# BLE-2541simple.net
KiCad netlist of a schematic drawn in Altium Designer
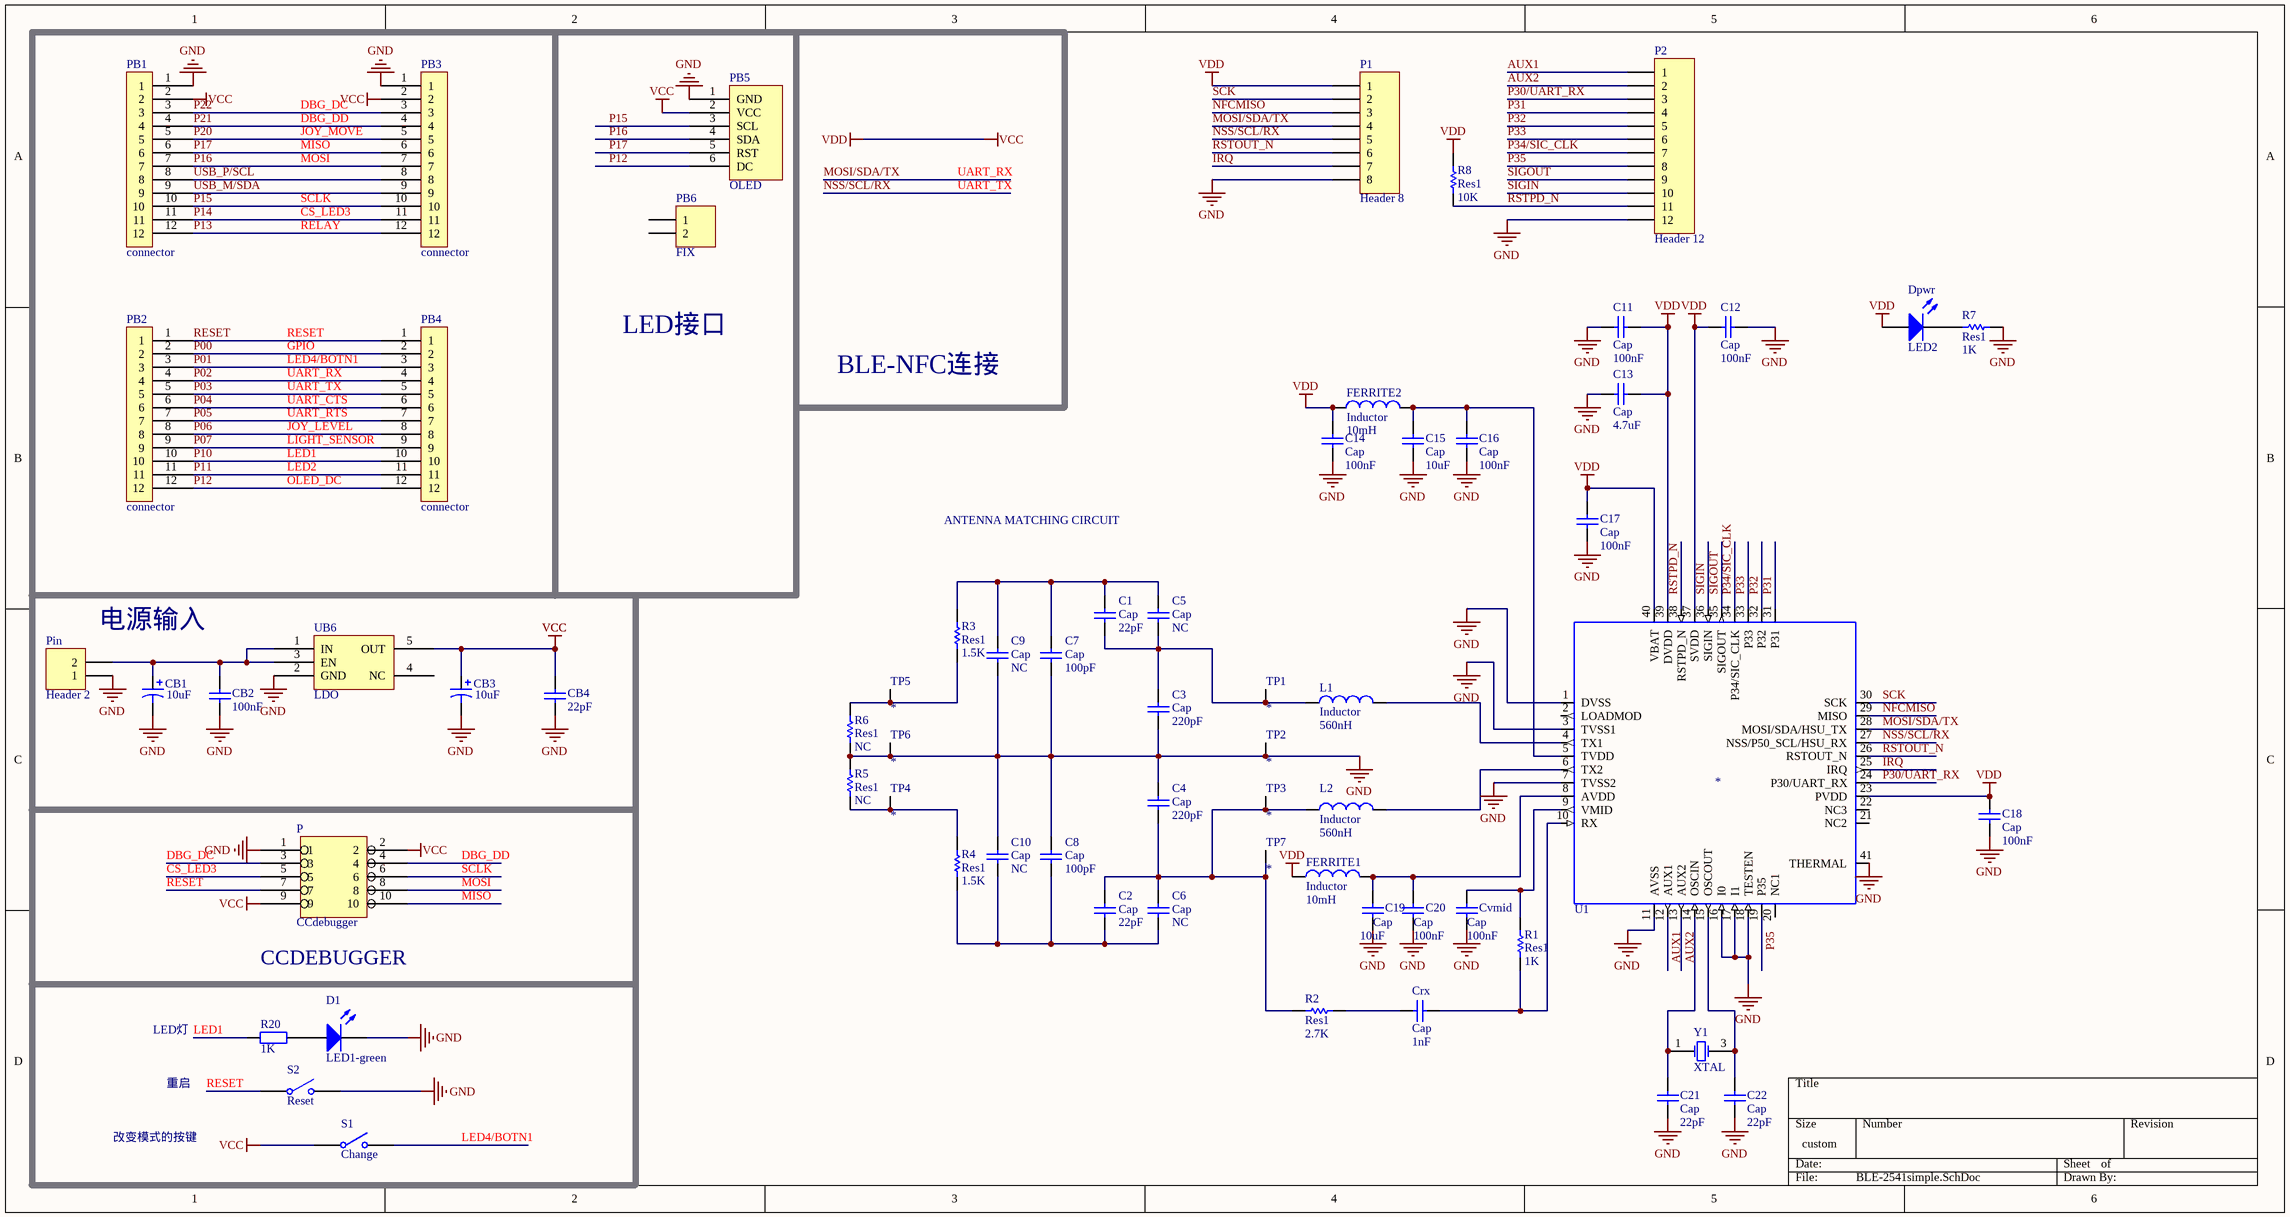
[diagram p0: BLE-2541simple.SchDoc]

(export (version "E")
  (design (tool "Eeschema 10.0.6"))
  (components
    (comp (ref "C1")
      (value "Cap")
      (footprint "6-0805_M")
      (description "Capacitor")
      (fields (field (name "ALTIUM_VALUE") "22pF") (field (name "PUBLISHER") "Altium Limited"))
      (libsource (lib "Miscellaneous Devices") (part "Cap"))
    )
    (comp (ref "C2")
      (value "Cap")
      (footprint "6-0805_M")
      (description "Capacitor")
      (fields (field (name "ALTIUM_VALUE") "22pF") (field (name "PUBLISHER") "Altium Limited"))
      (libsource (lib "Miscellaneous Devices") (part "Cap"))
    )
    (comp (ref "C3")
      (value "Cap")
      (footprint "6-0805_M")
      (description "Capacitor")
      (fields (field (name "ALTIUM_VALUE") "220pF") (field (name "PUBLISHER") "Altium Limited"))
      (libsource (lib "Miscellaneous Devices") (part "Cap"))
    )
    (comp (ref "C4")
      (value "Cap")
      (footprint "6-0805_M")
      (description "Capacitor")
      (fields (field (name "ALTIUM_VALUE") "220pF") (field (name "PUBLISHER") "Altium Limited"))
      (libsource (lib "Miscellaneous Devices") (part "Cap"))
    )
    (comp (ref "C5")
      (value "Cap")
      (footprint "6-0805_M")
      (description "Capacitor")
      (fields (field (name "ALTIUM_VALUE") "NC") (field (name "PUBLISHER") "Altium Limited"))
      (libsource (lib "Miscellaneous Devices") (part "Cap"))
    )
    (comp (ref "C6")
      (value "Cap")
      (footprint "6-0805_M")
      (description "Capacitor")
      (fields (field (name "ALTIUM_VALUE") "NC") (field (name "PUBLISHER") "Altium Limited"))
      (libsource (lib "Miscellaneous Devices") (part "Cap"))
    )
    (comp (ref "C7")
      (value "Cap")
      (footprint "6-0805_M")
      (description "Capacitor")
      (fields (field (name "ALTIUM_VALUE") "100pF") (field (name "PUBLISHER") "Altium Limited"))
      (libsource (lib "Miscellaneous Devices") (part "Cap"))
    )
    (comp (ref "C8")
      (value "Cap")
      (footprint "6-0805_M")
      (description "Capacitor")
      (fields (field (name "ALTIUM_VALUE") "100pF") (field (name "PUBLISHER") "Altium Limited"))
      (libsource (lib "Miscellaneous Devices") (part "Cap"))
    )
    (comp (ref "C9")
      (value "Cap")
      (footprint "6-0805_M")
      (description "Capacitor")
      (fields (field (name "ALTIUM_VALUE") "NC") (field (name "PUBLISHER") "Altium Limited"))
      (libsource (lib "Miscellaneous Devices") (part "Cap"))
    )
    (comp (ref "C10")
      (value "Cap")
      (footprint "6-0805_M")
      (description "Capacitor")
      (fields (field (name "ALTIUM_VALUE") "NC") (field (name "PUBLISHER") "Altium Limited"))
      (libsource (lib "Miscellaneous Devices") (part "Cap"))
    )
    (comp (ref "C11")
      (value "Cap")
      (footprint "6-0805_M")
      (description "Capacitor")
      (fields (field (name "ALTIUM_VALUE") "100nF") (field (name "PUBLISHER") "Altium Limited"))
      (libsource (lib "Miscellaneous Devices") (part "Cap"))
    )
    (comp (ref "C12")
      (value "Cap")
      (footprint "6-0805_M")
      (description "Capacitor")
      (fields (field (name "ALTIUM_VALUE") "100nF") (field (name "PUBLISHER") "Altium Limited"))
      (libsource (lib "Miscellaneous Devices") (part "Cap"))
    )
    (comp (ref "C13")
      (value "Cap")
      (footprint "6-0805_M")
      (description "Capacitor")
      (fields (field (name "ALTIUM_VALUE") "4.7uF") (field (name "PUBLISHER") "Altium Limited"))
      (libsource (lib "Miscellaneous Devices") (part "Cap"))
    )
    (comp (ref "C14")
      (value "Cap")
      (footprint "6-0805_M")
      (description "Capacitor")
      (fields (field (name "ALTIUM_VALUE") "100nF") (field (name "PUBLISHER") "Altium Limited"))
      (libsource (lib "Miscellaneous Devices") (part "Cap"))
    )
    (comp (ref "C15")
      (value "Cap")
      (footprint "6-0805_M")
      (description "Capacitor")
      (fields (field (name "ALTIUM_VALUE") "10uF") (field (name "PUBLISHER") "Altium Limited"))
      (libsource (lib "Miscellaneous Devices") (part "Cap"))
    )
    (comp (ref "C16")
      (value "Cap")
      (footprint "6-0805_M")
      (description "Capacitor")
      (fields (field (name "ALTIUM_VALUE") "100nF") (field (name "PUBLISHER") "Altium Limited"))
      (libsource (lib "Miscellaneous Devices") (part "Cap"))
    )
    (comp (ref "C17")
      (value "Cap")
      (footprint "6-0805_M")
      (description "Capacitor")
      (fields (field (name "ALTIUM_VALUE") "100nF") (field (name "PUBLISHER") "Altium Limited"))
      (libsource (lib "Miscellaneous Devices") (part "Cap"))
    )
    (comp (ref "C18")
      (value "Cap")
      (footprint "6-0805_M")
      (description "Capacitor")
      (fields (field (name "ALTIUM_VALUE") "100nF") (field (name "PUBLISHER") "Altium Limited"))
      (libsource (lib "Miscellaneous Devices") (part "Cap"))
    )
    (comp (ref "C19")
      (value "Cap")
      (footprint "6-0805_M")
      (description "Capacitor")
      (fields (field (name "ALTIUM_VALUE") "10uF") (field (name "PUBLISHER") "Altium Limited"))
      (libsource (lib "Miscellaneous Devices") (part "Cap"))
    )
    (comp (ref "C20")
      (value "Cap")
      (footprint "6-0805_M")
      (description "Capacitor")
      (fields (field (name "ALTIUM_VALUE") "100nF") (field (name "PUBLISHER") "Altium Limited"))
      (libsource (lib "Miscellaneous Devices") (part "Cap"))
    )
    (comp (ref "C21")
      (value "Cap")
      (footprint "6-0805_M")
      (description "Capacitor")
      (fields (field (name "ALTIUM_VALUE") "22pF") (field (name "PUBLISHER") "Altium Limited"))
      (libsource (lib "Miscellaneous Devices") (part "Cap"))
    )
    (comp (ref "C22")
      (value "Cap")
      (footprint "6-0805_M")
      (description "Capacitor")
      (fields (field (name "ALTIUM_VALUE") "22pF") (field (name "PUBLISHER") "Altium Limited"))
      (libsource (lib "Miscellaneous Devices") (part "Cap"))
    )
    (comp (ref "CB1")
      (value "10uF")
      (footprint "0805-SMALL")
      (description "Polarized Capacitor (Radial)")
      (fields (field (name "Comment") "Cap Pol1") (field (name "PUBLISHER") "Altium Limited"))
      (libsource (lib "Miscellaneous Devices") (part "Cap Pol1"))
    )
    (comp (ref "CB2")
      (value "100nF")
      (footprint "0805-SMALL")
      (description "Capacitor")
      (fields (field (name "Comment") "Cap") (field (name "PUBLISHER") "Altium Limited"))
      (libsource (lib "Miscellaneous Devices") (part "Cap"))
    )
    (comp (ref "CB3")
      (value "10uF")
      (footprint "0805-SMALL")
      (description "Polarized Capacitor (Radial)")
      (fields (field (name "Comment") "Cap Pol1") (field (name "PUBLISHER") "Altium Limited"))
      (libsource (lib "Miscellaneous Devices") (part "Cap Pol1"))
    )
    (comp (ref "CB4")
      (value "22pF")
      (footprint "0805-SMALL")
      (description "Capacitor")
      (fields (field (name "Comment") "Cap") (field (name "PUBLISHER") "Altium Limited"))
      (libsource (lib "Miscellaneous Devices") (part "Cap"))
    )
    (comp (ref "Crx")
      (value "Cap")
      (footprint "6-0805_M")
      (description "Capacitor")
      (fields (field (name "ALTIUM_VALUE") "1nF") (field (name "PUBLISHER") "Altium Limited"))
      (libsource (lib "Miscellaneous Devices") (part "Cap"))
    )
    (comp (ref "Cvmid")
      (value "Cap")
      (footprint "6-0805_M")
      (description "Capacitor")
      (fields (field (name "ALTIUM_VALUE") "100nF") (field (name "PUBLISHER") "Altium Limited"))
      (libsource (lib "Miscellaneous Devices") (part "Cap"))
    )
    (comp (ref "D1")
      (value "LED1-green")
      (footprint "3.2X1.6X1.1")
      (description "Typical RED, GREEN, YELLOW, AMBER GaAs LED")
      (fields (field (name "PUBLISHER") "Altium Limited"))
      (libsource (lib "Miscellaneous Devices") (part "LED2"))
    )
    (comp (ref "Dpwr")
      (value "LED2")
      (footprint "6-0805_M")
      (description "Typical RED, GREEN, YELLOW, AMBER GaAs LED")
      (fields (field (name "PUBLISHER") "Altium Limited"))
      (libsource (lib "Miscellaneous Devices") (part "LED2"))
    )
    (comp (ref "FERRITE1")
      (value "Inductor")
      (footprint "6-0805_M")
      (fields (field (name "ALTIUM_VALUE") "10mH") (field (name "PUBLISHER") "Altium Limited"))
      (libsource (lib "Miscellaneous Devices") (part "Inductor"))
    )
    (comp (ref "FERRITE2")
      (value "Inductor")
      (footprint "6-0805_M")
      (fields (field (name "ALTIUM_VALUE") "10mH") (field (name "PUBLISHER") "Altium Limited"))
      (libsource (lib "Miscellaneous Devices") (part "Inductor"))
    )
    (comp (ref "L1")
      (value "Inductor")
      (footprint "6-0805_M")
      (fields (field (name "ALTIUM_VALUE") "560nH") (field (name "PUBLISHER") "Altium Limited"))
      (libsource (lib "Miscellaneous Devices") (part "Inductor"))
    )
    (comp (ref "L2")
      (value "Inductor")
      (footprint "6-0805_M")
      (fields (field (name "ALTIUM_VALUE") "560nH") (field (name "PUBLISHER") "Altium Limited"))
      (libsource (lib "Miscellaneous Devices") (part "Inductor"))
    )
    (comp (ref "P")
      (value "CCdebugger")
      (footprint "M-IDC10")
      (libsource (lib "Schlib1") (part "CCdebugger"))
    )
    (comp (ref "P1")
      (value "Header 8")
      (footprint "HDR1X8")
      (description "Header, 8-Pin")
      (fields (field (name "PUBLISHER") "Altium Limited"))
      (libsource (lib "Miscellaneous Connectors") (part "Header 8"))
    )
    (comp (ref "P2")
      (value "Header 12")
      (footprint "HDR1X12")
      (description "Header, 12-Pin")
      (fields (field (name "PUBLISHER") "Altium Limited"))
      (libsource (lib "Miscellaneous Connectors") (part "Header 12"))
    )
    (comp (ref "PB1") (value "connector") (footprint "M-IDC12M") (libsource (lib "") (part "connector_1")))
    (comp (ref "PB2") (value "connector") (footprint "M-IDC12M") (libsource (lib "") (part "connector_1")))
    (comp (ref "PB3")
      (value "connector")
      (footprint "M-IDC12")
      (libsource (lib "Schlib1") (part "connector"))
    )
    (comp (ref "PB4")
      (value "connector")
      (footprint "M-IDC12")
      (libsource (lib "Schlib1") (part "connector"))
    )
    (comp (ref "PB5") (value "OLED") (footprint "M-SIP6") (libsource (lib "Schlib1") (part "OLED")))
    (comp (ref "PB6")
      (value "FIX")
      (footprint "M-SIP2")
      (description "Header, 2-Pin")
      (fields (field (name "PUBLISHER") "Altium Limited"))
      (libsource (lib "") (part "Header 2_1"))
    )
    (comp (ref "Pin")
      (value "Header 2")
      (footprint "M-SIP2")
      (description "Header, 2-Pin")
      (fields (field (name "PUBLISHER") "Altium Limited"))
      (libsource (lib "Miscellaneous Connectors") (part "Header 2"))
    )
    (comp (ref "R1")
      (value "Res1")
      (footprint "6-0805_M")
      (description "Resistor")
      (fields (field (name "ALTIUM_VALUE") "1K") (field (name "PUBLISHER") "Altium Limited"))
      (libsource (lib "Miscellaneous Devices") (part "Res1"))
    )
    (comp (ref "R2")
      (value "Res1")
      (footprint "6-0805_M")
      (description "Resistor")
      (fields (field (name "ALTIUM_VALUE") "2.7K") (field (name "PUBLISHER") "Altium Limited"))
      (libsource (lib "Miscellaneous Devices") (part "Res1"))
    )
    (comp (ref "R3")
      (value "Res1")
      (footprint "6-0805_M")
      (description "Resistor")
      (fields (field (name "ALTIUM_VALUE") "1.5K") (field (name "PUBLISHER") "Altium Limited"))
      (libsource (lib "Miscellaneous Devices") (part "Res1"))
    )
    (comp (ref "R4")
      (value "Res1")
      (footprint "6-0805_M")
      (description "Resistor")
      (fields (field (name "ALTIUM_VALUE") "1.5K") (field (name "PUBLISHER") "Altium Limited"))
      (libsource (lib "Miscellaneous Devices") (part "Res1"))
    )
    (comp (ref "R5")
      (value "Res1")
      (footprint "6-0805_M")
      (description "Resistor")
      (fields (field (name "ALTIUM_VALUE") "NC") (field (name "PUBLISHER") "Altium Limited"))
      (libsource (lib "Miscellaneous Devices") (part "Res1"))
    )
    (comp (ref "R6")
      (value "Res1")
      (footprint "6-0805_M")
      (description "Resistor")
      (fields (field (name "ALTIUM_VALUE") "NC") (field (name "PUBLISHER") "Altium Limited"))
      (libsource (lib "Miscellaneous Devices") (part "Res1"))
    )
    (comp (ref "R7")
      (value "Res1")
      (footprint "6-0805_M")
      (description "Resistor")
      (fields (field (name "ALTIUM_VALUE") "1K") (field (name "PUBLISHER") "Altium Limited"))
      (libsource (lib "Miscellaneous Devices") (part "Res1"))
    )
    (comp (ref "R8")
      (value "Res1")
      (footprint "6-0805_M")
      (description "Resistor")
      (fields (field (name "ALTIUM_VALUE") "10K") (field (name "PUBLISHER") "Altium Limited"))
      (libsource (lib "Miscellaneous Devices") (part "Res1"))
    )
    (comp (ref "R20")
      (value "1K")
      (footprint "0805-SMALL")
      (description "Resistor")
      (fields (field (name "Comment") "Res2") (field (name "PUBLISHER") "Altium Limited"))
      (libsource (lib "Miscellaneous Devices") (part "Res2"))
    )
    (comp (ref "S1")
      (value "Change")
      (footprint "MY-KEY1")
      (description "Single-Pole, Single-Throw Switch")
      (fields (field (name "PUBLISHER") "Altium Limited"))
      (libsource (lib "Miscellaneous Devices") (part "SW-SPST"))
    )
    (comp (ref "S2")
      (value "Reset")
      (footprint "MY-KEY1")
      (description "Single-Pole, Single-Throw Switch")
      (fields (field (name "PUBLISHER") "Altium Limited"))
      (libsource (lib "Miscellaneous Devices") (part "SW-SPST"))
    )
    (comp (ref "TP1")
      (value "*")
      (footprint "PCBComponent_1")
      (libsource (lib "microbuilder") (part "TESTPOINTPAD"))
    )
    (comp (ref "TP2")
      (value "*")
      (footprint "PCBComponent_1")
      (libsource (lib "microbuilder") (part "TESTPOINTPAD"))
    )
    (comp (ref "TP3")
      (value "*")
      (footprint "PCBComponent_1")
      (libsource (lib "microbuilder") (part "TESTPOINTPAD"))
    )
    (comp (ref "TP4")
      (value "*")
      (footprint "PCBComponent_1")
      (libsource (lib "microbuilder") (part "TESTPOINTPAD"))
    )
    (comp (ref "TP5")
      (value "*")
      (footprint "PCBComponent_1")
      (libsource (lib "microbuilder") (part "TESTPOINTPAD"))
    )
    (comp (ref "TP6")
      (value "*")
      (footprint "PCBComponent_1")
      (libsource (lib "microbuilder") (part "TESTPOINTPAD"))
    )
    (comp (ref "TP7")
      (value "*")
      (footprint "PCBComponent_1")
      (libsource (lib "microbuilder") (part "TESTPOINTPAD"))
    )
    (comp (ref "U1")
      (value "*")
      (footprint "QFN50P600X600X85_HS-41N")
      (libsource (lib "microbuilder") (part "PN532"))
    )
    (comp (ref "UB6") (value "LDO") (footprint "SOT23-5") (libsource (lib "Schlib1") (part "LDO")))
    (comp (ref "Y1")
      (value "XTAL")
      (footprint "CRYSTAL_3225")
      (description "Crystal Oscillator")
      (fields (field (name "PUBLISHER") "Altium Limited"))
      (libsource (lib "Miscellaneous Devices") (part "XTAL"))
    )
  )
  (nets
    (net (code "1") (name "/AUX1") (class "Default")
      (node (ref "P2") (pin "1") (pinfunction "1_1") (pintype "passive"))
      (node (ref "U1") (pin "12") (pinfunction "AUX1_12") (pintype "output"))
    )
    (net (code "2") (name "/AUX2") (class "Default")
      (node (ref "P2") (pin "2") (pinfunction "2_2") (pintype "passive"))
      (node (ref "U1") (pin "13") (pinfunction "AUX2_13") (pintype "output"))
    )
    (net (code "3") (name "/CS_LED3") (class "Default")
      (node (ref "P") (pin "5") (pinfunction "5_5") (pintype "passive"))
      (node (ref "PB1") (pin "11") (pinfunction "11_11") (pintype "passive"))
      (node (ref "PB3") (pin "11") (pinfunction "11_11") (pintype "passive"))
    )
    (net (code "4") (name "/DBG_DC") (class "Default")
      (node (ref "P") (pin "3") (pinfunction "3_3") (pintype "passive"))
      (node (ref "PB1") (pin "3") (pinfunction "3_3") (pintype "passive"))
      (node (ref "PB3") (pin "3") (pinfunction "3_3") (pintype "passive"))
    )
    (net (code "5") (name "/DBG_DD") (class "Default")
      (node (ref "P") (pin "4") (pinfunction "4_4") (pintype "passive"))
      (node (ref "PB1") (pin "4") (pinfunction "4_4") (pintype "passive"))
      (node (ref "PB3") (pin "4") (pinfunction "4_4") (pintype "passive"))
    )
    (net (code "6") (name "/GPIO") (class "Default")
      (node (ref "PB2") (pin "2") (pinfunction "2_2") (pintype "passive"))
      (node (ref "PB4") (pin "2") (pinfunction "2_2") (pintype "passive"))
    )
    (net (code "7") (name "/IRQ") (class "Default")
      (node (ref "P1") (pin "7") (pinfunction "7_7") (pintype "passive"))
      (node (ref "U1") (pin "25") (pinfunction "IRQ_25") (pintype "output"))
    )
    (net (code "8") (name "/JOY_LEVEL") (class "Default")
      (node (ref "PB2") (pin "8") (pinfunction "8_8") (pintype "passive"))
      (node (ref "PB4") (pin "8") (pinfunction "8_8") (pintype "passive"))
    )
    (net (code "9") (name "/JOY_MOVE") (class "Default")
      (node (ref "PB1") (pin "5") (pinfunction "5_5") (pintype "passive"))
      (node (ref "PB3") (pin "5") (pinfunction "5_5") (pintype "passive"))
    )
    (net (code "10") (name "/LED1") (class "Default")
      (node (ref "PB2") (pin "10") (pinfunction "10_10") (pintype "passive"))
      (node (ref "PB4") (pin "10") (pinfunction "10_10") (pintype "passive"))
      (node (ref "R20") (pin "1") (pinfunction "1_1") (pintype "passive"))
    )
    (net (code "11") (name "/LED2") (class "Default")
      (node (ref "PB2") (pin "11") (pinfunction "11_11") (pintype "passive"))
      (node (ref "PB4") (pin "11") (pinfunction "11_11") (pintype "passive"))
    )
    (net (code "12") (name "/LED4{slash}BOTN1") (class "Default")
      (node (ref "PB2") (pin "3") (pinfunction "3_3") (pintype "passive"))
      (node (ref "PB4") (pin "3") (pinfunction "3_3") (pintype "passive"))
      (node (ref "S1") (pin "2") (pinfunction "NO_2") (pintype "passive"))
    )
    (net (code "13") (name "/LIGHT_SENSOR") (class "Default")
      (node (ref "PB2") (pin "9") (pinfunction "9_9") (pintype "passive"))
      (node (ref "PB4") (pin "9") (pinfunction "9_9") (pintype "passive"))
    )
    (net (code "14") (name "/MISO") (class "Default")
      (node (ref "P") (pin "10") (pinfunction "10_10") (pintype "passive"))
      (node (ref "PB1") (pin "6") (pinfunction "6_6") (pintype "passive"))
      (node (ref "PB3") (pin "6") (pinfunction "6_6") (pintype "passive"))
      (node (ref "PB5") (pin "5") (pinfunction "RST_5") (pintype "passive"))
    )
    (net (code "15") (name "/MOSI") (class "Default")
      (node (ref "P") (pin "8") (pinfunction "8_8") (pintype "passive"))
      (node (ref "PB1") (pin "7") (pinfunction "7_7") (pintype "passive"))
      (node (ref "PB3") (pin "7") (pinfunction "7_7") (pintype "passive"))
      (node (ref "PB5") (pin "4") (pinfunction "SDA_4") (pintype "passive"))
    )
    (net (code "16") (name "/MOSI{slash}SDA{slash}TX") (class "Default")
      (node (ref "P1") (pin "4") (pinfunction "4_4") (pintype "passive"))
      (node (ref "PB2") (pin "4") (pinfunction "4_4") (pintype "passive"))
      (node (ref "PB4") (pin "4") (pinfunction "4_4") (pintype "passive"))
      (node (ref "U1") (pin "28") (pinfunction "MOSI/SDA/HSU_TX_28") (pintype "bidirectional"))
    )
    (net (code "17") (name "/NFCMISO") (class "Default")
      (node (ref "P1") (pin "3") (pinfunction "3_3") (pintype "passive"))
      (node (ref "U1") (pin "29") (pinfunction "MISO_29") (pintype "bidirectional"))
    )
    (net (code "18") (name "/NSS{slash}SCL{slash}RX") (class "Default")
      (node (ref "P1") (pin "5") (pinfunction "5_5") (pintype "passive"))
      (node (ref "PB2") (pin "5") (pinfunction "5_5") (pintype "passive"))
      (node (ref "PB4") (pin "5") (pinfunction "5_5") (pintype "passive"))
      (node (ref "U1") (pin "27") (pinfunction "NSS/P50_SCL/HSU_RX_27") (pintype "bidirectional"))
    )
    (net (code "19") (name "/OLED_DC") (class "Default")
      (node (ref "PB2") (pin "12") (pinfunction "12_12") (pintype "passive"))
      (node (ref "PB4") (pin "12") (pinfunction "12_12") (pintype "passive"))
      (node (ref "PB5") (pin "6") (pinfunction "DC_6") (pintype "passive"))
    )
    (net (code "20") (name "/P04") (class "Default")
      (node (ref "PB2") (pin "6") (pinfunction "6_6") (pintype "passive"))
      (node (ref "PB4") (pin "6") (pinfunction "6_6") (pintype "passive"))
    )
    (net (code "21") (name "/P05") (class "Default")
      (node (ref "PB2") (pin "7") (pinfunction "7_7") (pintype "passive"))
      (node (ref "PB4") (pin "7") (pinfunction "7_7") (pintype "passive"))
    )
    (net (code "22") (name "/P13") (class "Default")
      (node (ref "PB1") (pin "12") (pinfunction "12_12") (pintype "passive"))
      (node (ref "PB3") (pin "12") (pinfunction "12_12") (pintype "passive"))
    )
    (net (code "23") (name "/P15") (class "Default")
      (node (ref "P") (pin "6") (pinfunction "6_6") (pintype "passive"))
      (node (ref "PB1") (pin "10") (pinfunction "10_10") (pintype "passive"))
      (node (ref "PB3") (pin "10") (pinfunction "10_10") (pintype "passive"))
      (node (ref "PB5") (pin "3") (pinfunction "SCL_3") (pintype "passive"))
    )
    (net (code "24") (name "/P30{slash}UART_RX") (class "Default")
      (node (ref "P2") (pin "3") (pinfunction "3_3") (pintype "passive"))
      (node (ref "U1") (pin "24") (pinfunction "P30/UART_RX_24") (pintype "bidirectional"))
    )
    (net (code "25") (name "/P31") (class "Default")
      (node (ref "P2") (pin "4") (pinfunction "4_4") (pintype "passive"))
      (node (ref "U1") (pin "31") (pinfunction "P31_31") (pintype "bidirectional"))
    )
    (net (code "26") (name "/P32") (class "Default")
      (node (ref "P2") (pin "5") (pinfunction "5_5") (pintype "passive"))
      (node (ref "U1") (pin "32") (pinfunction "P32_32") (pintype "bidirectional"))
    )
    (net (code "27") (name "/P33") (class "Default")
      (node (ref "P2") (pin "6") (pinfunction "6_6") (pintype "passive"))
      (node (ref "U1") (pin "33") (pinfunction "P33_33") (pintype "bidirectional"))
    )
    (net (code "28") (name "/P34{slash}SIC_CLK") (class "Default")
      (node (ref "P2") (pin "7") (pinfunction "7_7") (pintype "passive"))
      (node (ref "U1") (pin "34") (pinfunction "P34/SIC_CLK_34") (pintype "bidirectional"))
    )
    (net (code "29") (name "/P35") (class "Default")
      (node (ref "P2") (pin "8") (pinfunction "8_8") (pintype "passive"))
      (node (ref "U1") (pin "19") (pinfunction "P35_19") (pintype "bidirectional"))
    )
    (net (code "30") (name "/RESET") (class "Default")
      (node (ref "P") (pin "7") (pinfunction "7_7") (pintype "passive"))
      (node (ref "PB2") (pin "1") (pinfunction "1_1") (pintype "passive"))
      (node (ref "PB4") (pin "1") (pinfunction "1_1") (pintype "passive"))
      (node (ref "S2") (pin "1") (pinfunction "COMMON_1") (pintype "passive"))
    )
    (net (code "31") (name "/RSTOUT_N") (class "Default")
      (node (ref "P1") (pin "6") (pinfunction "6_6") (pintype "passive"))
      (node (ref "U1") (pin "26") (pinfunction "RSTOUT_N_26") (pintype "bidirectional"))
    )
    (net (code "32") (name "/RSTPD_N") (class "Default")
      (node (ref "P2") (pin "11") (pinfunction "11_11") (pintype "passive"))
      (node (ref "R8") (pin "2") (pinfunction "2_2") (pintype "passive"))
      (node (ref "U1") (pin "38") (pinfunction "RSTPD_N_38") (pintype "input"))
    )
    (net (code "33") (name "/SCK") (class "Default")
      (node (ref "P1") (pin "2") (pinfunction "2_2") (pintype "passive"))
      (node (ref "U1") (pin "30") (pinfunction "SCK_30") (pintype "bidirectional"))
    )
    (net (code "34") (name "/SIGIN") (class "Default")
      (node (ref "P2") (pin "10") (pinfunction "10_10") (pintype "passive"))
      (node (ref "U1") (pin "36") (pinfunction "SIGIN_36") (pintype "input"))
    )
    (net (code "35") (name "/SIGOUT") (class "Default")
      (node (ref "P2") (pin "9") (pinfunction "9_9") (pintype "passive"))
      (node (ref "U1") (pin "35") (pinfunction "SIGOUT_35") (pintype "output"))
    )
    (net (code "36") (name "/USB_M{slash}SDA") (class "Default")
      (node (ref "PB1") (pin "9") (pinfunction "9_9") (pintype "passive"))
      (node (ref "PB3") (pin "9") (pinfunction "9_9") (pintype "passive"))
    )
    (net (code "37") (name "/USB_P{slash}SCL") (class "Default")
      (node (ref "PB1") (pin "8") (pinfunction "8_8") (pintype "passive"))
      (node (ref "PB3") (pin "8") (pinfunction "8_8") (pintype "passive"))
    )
    (net (code "38") (name "GND") (class "Default")
      (node (ref "C10") (pin "2") (pinfunction "2_2") (pintype "passive"))
      (node (ref "C11") (pin "1") (pinfunction "1_1") (pintype "passive"))
      (node (ref "C12") (pin "2") (pinfunction "2_2") (pintype "passive"))
      (node (ref "C13") (pin "1") (pinfunction "1_1") (pintype "passive"))
      (node (ref "C14") (pin "1") (pinfunction "1_1") (pintype "passive"))
      (node (ref "C15") (pin "1") (pinfunction "1_1") (pintype "passive"))
      (node (ref "C16") (pin "1") (pinfunction "1_1") (pintype "passive"))
      (node (ref "C17") (pin "1") (pinfunction "1_1") (pintype "passive"))
      (node (ref "C18") (pin "2") (pinfunction "2_2") (pintype "passive"))
      (node (ref "C19") (pin "1") (pinfunction "1_1") (pintype "passive"))
      (node (ref "C20") (pin "1") (pinfunction "1_1") (pintype "passive"))
      (node (ref "C21") (pin "2") (pinfunction "2_2") (pintype "passive"))
      (node (ref "C22") (pin "2") (pinfunction "2_2") (pintype "passive"))
      (node (ref "C3") (pin "1") (pinfunction "1_1") (pintype "passive"))
      (node (ref "C4") (pin "2") (pinfunction "2_2") (pintype "passive"))
      (node (ref "C7") (pin "1") (pinfunction "1_1") (pintype "passive"))
      (node (ref "C8") (pin "2") (pinfunction "2_2") (pintype "passive"))
      (node (ref "C9") (pin "1") (pinfunction "1_1") (pintype "passive"))
      (node (ref "CB1") (pin "2") (pinfunction "2_2") (pintype "passive"))
      (node (ref "CB2") (pin "1") (pinfunction "1_1") (pintype "passive"))
      (node (ref "CB3") (pin "2") (pinfunction "2_2") (pintype "passive"))
      (node (ref "CB4") (pin "1") (pinfunction "1_1") (pintype "passive"))
      (node (ref "Cvmid") (pin "1") (pinfunction "1_1") (pintype "passive"))
      (node (ref "D1") (pin "2") (pinfunction "K_2") (pintype "passive"))
      (node (ref "P") (pin "1") (pinfunction "1_1") (pintype "passive"))
      (node (ref "P1") (pin "8") (pinfunction "8_8") (pintype "passive"))
      (node (ref "P2") (pin "12") (pinfunction "12_12") (pintype "passive"))
      (node (ref "PB1") (pin "1") (pinfunction "1_1") (pintype "passive"))
      (node (ref "PB3") (pin "1") (pinfunction "1_1") (pintype "passive"))
      (node (ref "PB5") (pin "1") (pinfunction "GND_1") (pintype "passive"))
      (node (ref "Pin") (pin "1") (pinfunction "1_1") (pintype "passive"))
      (node (ref "R5") (pin "2") (pinfunction "2_2") (pintype "passive"))
      (node (ref "R6") (pin "1") (pinfunction "1_1") (pintype "passive"))
      (node (ref "R7") (pin "2") (pinfunction "2_2") (pintype "passive"))
      (node (ref "S2") (pin "2") (pinfunction "NO_2") (pintype "passive"))
      (node (ref "TP2") (pin "1") (pinfunction "P$1_1") (pintype "passive"))
      (node (ref "TP6") (pin "1") (pinfunction "P$1_1") (pintype "passive"))
      (node (ref "U1") (pin "1") (pinfunction "DVSS_1") (pintype "power_in"))
      (node (ref "U1") (pin "11") (pinfunction "AVSS_11") (pintype "power_in"))
      (node (ref "U1") (pin "16") (pinfunction "I0_16") (pintype "input"))
      (node (ref "U1") (pin "17") (pinfunction "I1_17") (pintype "input"))
      (node (ref "U1") (pin "18") (pinfunction "TESTEN_18") (pintype "input"))
      (node (ref "U1") (pin "3") (pinfunction "TVSS1_3") (pintype "power_in"))
      (node (ref "U1") (pin "41") (pinfunction "THERMAL_41") (pintype "power_in"))
      (node (ref "U1") (pin "7") (pinfunction "TVSS2_7") (pintype "power_in"))
      (node (ref "UB6") (pin "2") (pinfunction "GND_2") (pintype "passive"))
    )
    (net (code "39") (name "Net-(C1-Pad2)") (class "Default")
      (node (ref "C1") (pin "2") (pinfunction "2_2") (pintype "passive"))
      (node (ref "C5") (pin "2") (pinfunction "2_2") (pintype "passive"))
      (node (ref "C7") (pin "2") (pinfunction "2_2") (pintype "passive"))
      (node (ref "C9") (pin "2") (pinfunction "2_2") (pintype "passive"))
      (node (ref "R3") (pin "2") (pinfunction "2_2") (pintype "passive"))
    )
    (net (code "40") (name "Net-(C10-Pad1)") (class "Default")
      (node (ref "C10") (pin "1") (pinfunction "1_1") (pintype "passive"))
      (node (ref "C2") (pin "1") (pinfunction "1_1") (pintype "passive"))
      (node (ref "C6") (pin "1") (pinfunction "1_1") (pintype "passive"))
      (node (ref "C8") (pin "1") (pinfunction "1_1") (pintype "passive"))
      (node (ref "R4") (pin "1") (pinfunction "1_1") (pintype "passive"))
    )
    (net (code "41") (name "Net-(Crx-Pad2)") (class "Default")
      (node (ref "Crx") (pin "2") (pinfunction "2_2") (pintype "passive"))
      (node (ref "R2") (pin "1") (pinfunction "1_1") (pintype "passive"))
    )
    (net (code "42") (name "Net-(D1-A)") (class "Default")
      (node (ref "D1") (pin "1") (pinfunction "A_1") (pintype "passive"))
      (node (ref "R20") (pin "2") (pinfunction "2_2") (pintype "passive"))
    )
    (net (code "43") (name "Net-(Dpwr-K)") (class "Default")
      (node (ref "Dpwr") (pin "2") (pinfunction "K_2") (pintype "passive"))
      (node (ref "R7") (pin "1") (pinfunction "1_1") (pintype "passive"))
    )
    (net (code "44") (name "Net-(TP1-P$1)") (class "Default")
      (node (ref "C1") (pin "1") (pinfunction "1_1") (pintype "passive"))
      (node (ref "C3") (pin "2") (pinfunction "2_2") (pintype "passive"))
      (node (ref "C5") (pin "1") (pinfunction "1_1") (pintype "passive"))
      (node (ref "L1") (pin "1") (pinfunction "1_1") (pintype "passive"))
      (node (ref "TP1") (pin "1") (pinfunction "P$1_1") (pintype "passive"))
    )
    (net (code "45") (name "Net-(TP3-P$1)") (class "Default")
      (node (ref "C2") (pin "2") (pinfunction "2_2") (pintype "passive"))
      (node (ref "C4") (pin "1") (pinfunction "1_1") (pintype "passive"))
      (node (ref "C6") (pin "2") (pinfunction "2_2") (pintype "passive"))
      (node (ref "L2") (pin "1") (pinfunction "1_1") (pintype "passive"))
      (node (ref "R2") (pin "2") (pinfunction "2_2") (pintype "passive"))
      (node (ref "TP3") (pin "1") (pinfunction "P$1_1") (pintype "passive"))
      (node (ref "TP7") (pin "1") (pinfunction "P$1_1") (pintype "passive"))
    )
    (net (code "46") (name "Net-(TP4-P$1)") (class "Default")
      (node (ref "R4") (pin "2") (pinfunction "2_2") (pintype "passive"))
      (node (ref "R5") (pin "1") (pinfunction "1_1") (pintype "passive"))
      (node (ref "TP4") (pin "1") (pinfunction "P$1_1") (pintype "passive"))
    )
    (net (code "47") (name "Net-(TP5-P$1)") (class "Default")
      (node (ref "R3") (pin "1") (pinfunction "1_1") (pintype "passive"))
      (node (ref "R6") (pin "2") (pinfunction "2_2") (pintype "passive"))
      (node (ref "TP5") (pin "1") (pinfunction "P$1_1") (pintype "passive"))
    )
    (net (code "48") (name "Net-(U1-AVDD)") (class "Default")
      (node (ref "C19") (pin "2") (pinfunction "2_2") (pintype "passive"))
      (node (ref "C20") (pin "2") (pinfunction "2_2") (pintype "passive"))
      (node (ref "FERRITE1") (pin "2") (pinfunction "2_2") (pintype "passive"))
      (node (ref "U1") (pin "8") (pinfunction "AVDD_8") (pintype "power_in"))
    )
    (net (code "49") (name "Net-(U1-OSCIN)") (class "Default")
      (node (ref "C21") (pin "1") (pinfunction "1_1") (pintype "passive"))
      (node (ref "U1") (pin "14") (pinfunction "OSCIN_14") (pintype "input"))
      (node (ref "Y1") (pin "1") (pinfunction "OSC1_1") (pintype "passive"))
    )
    (net (code "50") (name "Net-(U1-OSCOUT)") (class "Default")
      (node (ref "C22") (pin "1") (pinfunction "1_1") (pintype "passive"))
      (node (ref "U1") (pin "15") (pinfunction "OSCOUT_15") (pintype "output"))
      (node (ref "Y1") (pin "3") (pinfunction "OSC2_3") (pintype "passive"))
    )
    (net (code "51") (name "Net-(U1-RX)") (class "Default")
      (node (ref "Crx") (pin "1") (pinfunction "1_1") (pintype "passive"))
      (node (ref "R1") (pin "1") (pinfunction "1_1") (pintype "passive"))
      (node (ref "U1") (pin "10") (pinfunction "RX_10") (pintype "input"))
    )
    (net (code "52") (name "Net-(U1-TVDD)") (class "Default")
      (node (ref "C15") (pin "2") (pinfunction "2_2") (pintype "passive"))
      (node (ref "C16") (pin "2") (pinfunction "2_2") (pintype "passive"))
      (node (ref "FERRITE2") (pin "2") (pinfunction "2_2") (pintype "passive"))
      (node (ref "U1") (pin "5") (pinfunction "TVDD_5") (pintype "power_in"))
    )
    (net (code "53") (name "Net-(U1-TX1)") (class "Default")
      (node (ref "L1") (pin "2") (pinfunction "2_2") (pintype "passive"))
      (node (ref "U1") (pin "4") (pinfunction "TX1_4") (pintype "output"))
    )
    (net (code "54") (name "Net-(U1-TX2)") (class "Default")
      (node (ref "L2") (pin "2") (pinfunction "2_2") (pintype "passive"))
      (node (ref "U1") (pin "6") (pinfunction "TX2_6") (pintype "output"))
    )
    (net (code "55") (name "Net-(U1-VMID)") (class "Default")
      (node (ref "Cvmid") (pin "2") (pinfunction "2_2") (pintype "passive"))
      (node (ref "R1") (pin "2") (pinfunction "2_2") (pintype "passive"))
      (node (ref "U1") (pin "9") (pinfunction "VMID_9") (pintype "output"))
    )
    (net (code "56") (name "Net-(UB6-EN)") (class "Default")
      (node (ref "CB1") (pin "1") (pinfunction "1_1") (pintype "passive"))
      (node (ref "CB2") (pin "2") (pinfunction "2_2") (pintype "passive"))
      (node (ref "Pin") (pin "2") (pinfunction "2_2") (pintype "passive"))
      (node (ref "UB6") (pin "1") (pinfunction "IN_1") (pintype "passive"))
      (node (ref "UB6") (pin "3") (pinfunction "EN_3") (pintype "passive"))
    )
    (net (code "57") (name "VCC") (class "Default")
      (node (ref "C11") (pin "2") (pinfunction "2_2") (pintype "passive"))
      (node (ref "C12") (pin "1") (pinfunction "1_1") (pintype "passive"))
      (node (ref "C13") (pin "2") (pinfunction "2_2") (pintype "passive"))
      (node (ref "C14") (pin "2") (pinfunction "2_2") (pintype "passive"))
      (node (ref "C17") (pin "2") (pinfunction "2_2") (pintype "passive"))
      (node (ref "C18") (pin "1") (pinfunction "1_1") (pintype "passive"))
      (node (ref "CB3") (pin "1") (pinfunction "1_1") (pintype "passive"))
      (node (ref "CB4") (pin "2") (pinfunction "2_2") (pintype "passive"))
      (node (ref "Dpwr") (pin "1") (pinfunction "A_1") (pintype "passive"))
      (node (ref "FERRITE1") (pin "1") (pinfunction "1_1") (pintype "passive"))
      (node (ref "FERRITE2") (pin "1") (pinfunction "1_1") (pintype "passive"))
      (node (ref "P") (pin "2") (pinfunction "2_2") (pintype "passive"))
      (node (ref "P") (pin "9") (pinfunction "9_9") (pintype "passive"))
      (node (ref "P1") (pin "1") (pinfunction "1_1") (pintype "passive"))
      (node (ref "PB1") (pin "2") (pinfunction "2_2") (pintype "passive"))
      (node (ref "PB3") (pin "2") (pinfunction "2_2") (pintype "passive"))
      (node (ref "PB5") (pin "2") (pinfunction "VCC_2") (pintype "passive"))
      (node (ref "R8") (pin "1") (pinfunction "1_1") (pintype "passive"))
      (node (ref "S1") (pin "1") (pinfunction "COMMON_1") (pintype "passive"))
      (node (ref "U1") (pin "23") (pinfunction "PVDD_23") (pintype "power_in"))
      (node (ref "U1") (pin "37") (pinfunction "SVDD_37") (pintype "power_in"))
      (node (ref "U1") (pin "39") (pinfunction "DVDD_39") (pintype "power_in"))
      (node (ref "U1") (pin "40") (pinfunction "VBAT_40") (pintype "power_in"))
      (node (ref "UB6") (pin "5") (pinfunction "OUT_5") (pintype "passive"))
    )
    (net (code "58") (name "unconnected-(PB6-Pad1)") (class "Default")
      (node (ref "PB6") (pin "1") (pinfunction "1_1") (pintype "passive"))
    )
    (net (code "59") (name "unconnected-(PB6-Pad2)") (class "Default")
      (node (ref "PB6") (pin "2") (pinfunction "2_2") (pintype "passive"))
    )
    (net (code "60") (name "unconnected-(U1-LOADMOD-Pad2)") (class "Default")
      (node (ref "U1") (pin "2") (pinfunction "LOADMOD_2") (pintype "output"))
    )
    (net (code "61") (name "unconnected-(U1-NC1-Pad20)") (class "Default")
      (node (ref "U1") (pin "20") (pinfunction "NC1_20") (pintype "passive"))
    )
    (net (code "62") (name "unconnected-(U1-NC2-Pad21)") (class "Default")
      (node (ref "U1") (pin "21") (pinfunction "NC2_21") (pintype "passive"))
    )
    (net (code "63") (name "unconnected-(U1-NC3-Pad22)") (class "Default")
      (node (ref "U1") (pin "22") (pinfunction "NC3_22") (pintype "passive"))
    )
    (net (code "64") (name "unconnected-(UB6-NC-Pad4)") (class "Default")
      (node (ref "UB6") (pin "4") (pinfunction "NC_4") (pintype "passive"))
    )
  )
)
